# Node.net
KiCad netlist of a schematic drawn in EAGLE
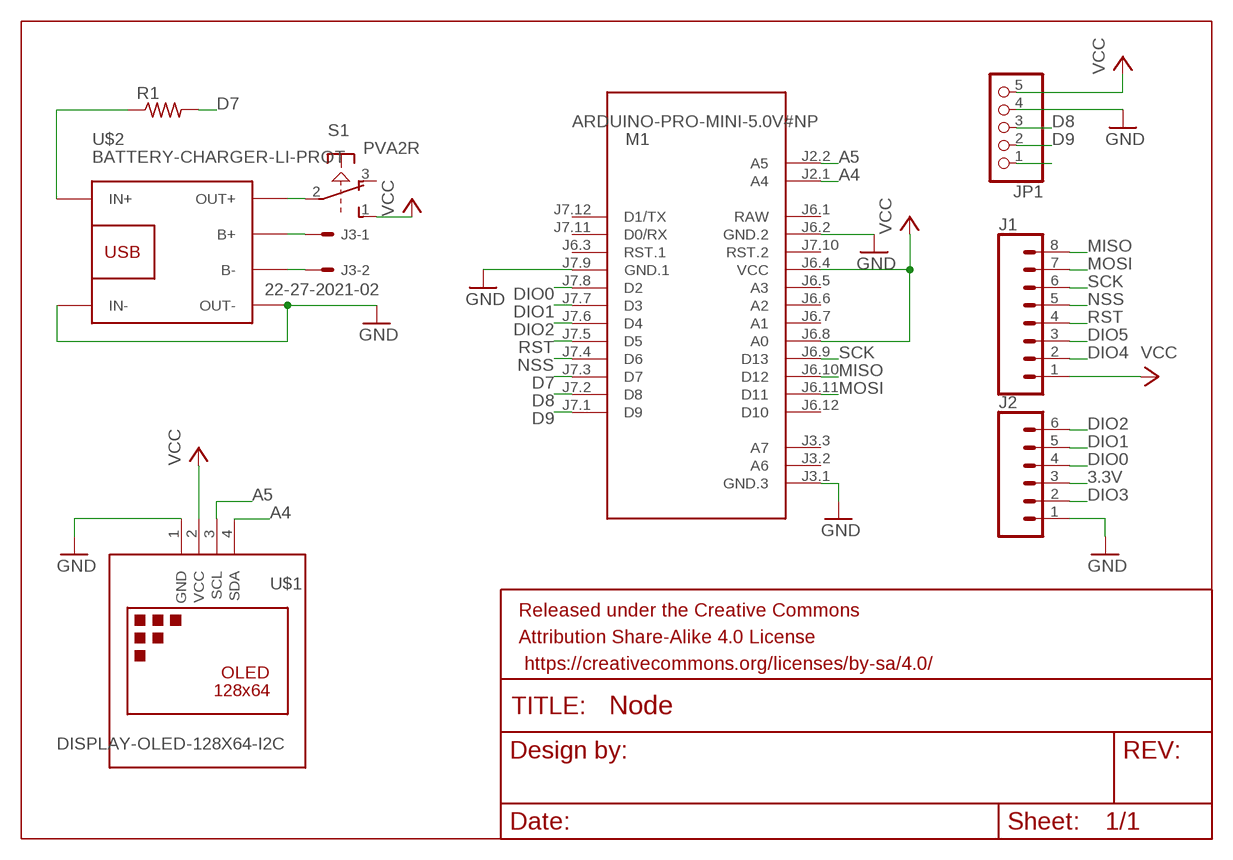
[diagram p0: schematic, sheet 1]

(export (version "E")
  (design (tool "Eeschema 10.0.6"))
  (components
    (comp (ref "FRAME1")
      (value "FRAME-LEDGER")
      (footprint "eagle-import:CREATIVE_COMMONS")
      (libsource (lib "eagle-import") (part "FRAME-LEDGER"))
    )
    (comp (ref "J1")
      (value "CONN_08\"")
      (footprint "eagle-import:1X08")
      (libsource (lib "eagle-import") (part "CONN_08{dblquote}"))
    )
    (comp (ref "J2")
      (value "CONN_06SILK_FEMALE_PTH")
      (footprint "eagle-import:1X06")
      (libsource (lib "eagle-import") (part "CONN_06SILK_FEMALE_PTH"))
    )
    (comp (ref "J3")
      (value "22-27-2021-02")
      (footprint "eagle-import:6410-02")
      (fields (field (name "MF") "MOLEX"))
      (libsource (lib "eagle-import") (part "22-?-0227-2021"))
    )
    (comp (ref "JP1")
      (value "PINHD-1X5/90")
      (footprint "eagle-import:1X05_90")
      (libsource (lib "eagle-import") (part "PINHD-1X5/90"))
    )
    (comp (ref "M1")
      (value "ARDUINO-PRO-MINI-5.0V#NP")
      (footprint "eagle-import:ARDUINO-PRO-MINI#NP")
      (libsource (lib "eagle-import") (part "ARDUINO-PRO-MINI-#NP5.0V"))
    )
    (comp (ref "R1")
      (value "R-US_R1206")
      (footprint "eagle-import:R1206")
      (libsource (lib "eagle-import") (part "R-US_R1206"))
    )
    (comp (ref "S1")
      (value "PVA2R")
      (footprint "eagle-import:PVA2R")
      (libsource (lib "eagle-import") (part "PVA2R"))
    )
    (comp (ref "U$1")
      (value "DISPLAY-OLED-128X64-I2C")
      (footprint "eagle-import:DISPLAY-OLED-128X64-I2C")
      (libsource (lib "eagle-import") (part "DISPLAY-OLED-128X64-I2C"))
    )
    (comp (ref "U$2")
      (value "BATTERY-CHARGER-LI-PROT")
      (footprint "eagle-import:BATTERY-CHARGER-LI-PROT")
      (libsource (lib "eagle-import") (part "BATTERY-CHARGER-LI-PROT"))
    )
  )
  (nets
    (net (code "1") (name "/3.3V") (class "Default")
      (node (ref "J2") (pin "3") (pinfunction "3_3") (pintype "passive"))
    )
    (net (code "2") (name "/A4") (class "Default")
      (node (ref "M1") (pin "J2.1") (pinfunction "A4_J2.1") (pintype "bidirectional"))
      (node (ref "U$1") (pin "4") (pinfunction "SDA_4") (pintype "bidirectional"))
    )
    (net (code "3") (name "/A5") (class "Default")
      (node (ref "M1") (pin "J2.2") (pinfunction "A5_J2.2") (pintype "bidirectional"))
      (node (ref "U$1") (pin "3") (pinfunction "SCL_3") (pintype "bidirectional"))
    )
    (net (code "4") (name "/D7") (class "Default")
      (node (ref "M1") (pin "J7.3") (pinfunction "D7_J7.3") (pintype "bidirectional"))
      (node (ref "R1") (pin "2") (pinfunction "2_2") (pintype "passive"))
    )
    (net (code "5") (name "/D8") (class "Default")
      (node (ref "JP1") (pin "3") (pinfunction "3_3") (pintype "passive"))
      (node (ref "M1") (pin "J7.2") (pinfunction "D8_J7.2") (pintype "bidirectional"))
    )
    (net (code "6") (name "/D9") (class "Default")
      (node (ref "JP1") (pin "2") (pinfunction "2_2") (pintype "passive"))
      (node (ref "M1") (pin "J7.1") (pinfunction "D9_J7.1") (pintype "bidirectional"))
    )
    (net (code "7") (name "/DIO0") (class "Default")
      (node (ref "J2") (pin "4") (pinfunction "4_4") (pintype "passive"))
      (node (ref "M1") (pin "J7.8") (pinfunction "D2_J7.8") (pintype "bidirectional"))
    )
    (net (code "8") (name "/DIO1") (class "Default")
      (node (ref "J2") (pin "5") (pinfunction "5_5") (pintype "passive"))
      (node (ref "M1") (pin "J7.7") (pinfunction "D3_J7.7") (pintype "bidirectional"))
    )
    (net (code "9") (name "/DIO2") (class "Default")
      (node (ref "J2") (pin "6") (pinfunction "6_6") (pintype "passive"))
      (node (ref "M1") (pin "J7.6") (pinfunction "D4_J7.6") (pintype "bidirectional"))
    )
    (net (code "10") (name "/DIO3") (class "Default")
      (node (ref "J2") (pin "2") (pinfunction "2_2") (pintype "passive"))
    )
    (net (code "11") (name "/DIO4") (class "Default")
      (node (ref "J1") (pin "2") (pinfunction "2_2") (pintype "passive"))
    )
    (net (code "12") (name "/DIO5") (class "Default")
      (node (ref "J1") (pin "3") (pinfunction "3_3") (pintype "passive"))
    )
    (net (code "13") (name "/MISO") (class "Default")
      (node (ref "J1") (pin "8") (pinfunction "8_8") (pintype "passive"))
      (node (ref "M1") (pin "J6.10") (pinfunction "D12_J6.10") (pintype "bidirectional"))
    )
    (net (code "14") (name "/MOSI") (class "Default")
      (node (ref "J1") (pin "7") (pinfunction "7_7") (pintype "passive"))
      (node (ref "M1") (pin "J6.11") (pinfunction "D11_J6.11") (pintype "bidirectional"))
    )
    (net (code "15") (name "/NSS") (class "Default")
      (node (ref "J1") (pin "5") (pinfunction "5_5") (pintype "passive"))
      (node (ref "M1") (pin "J7.4") (pinfunction "D6_J7.4") (pintype "bidirectional"))
    )
    (net (code "16") (name "/RAW") (class "Default")
      (node (ref "M1") (pin "J6.1") (pinfunction "RAW_J6.1") (pintype "power_in"))
    )
    (net (code "17") (name "/RST") (class "Default")
      (node (ref "J1") (pin "4") (pinfunction "4_4") (pintype "passive"))
      (node (ref "M1") (pin "J7.5") (pinfunction "D5_J7.5") (pintype "bidirectional"))
    )
    (net (code "18") (name "/SCK") (class "Default")
      (node (ref "J1") (pin "6") (pinfunction "6_6") (pintype "passive"))
      (node (ref "M1") (pin "J6.9") (pinfunction "D13_J6.9") (pintype "bidirectional"))
    )
    (net (code "19") (name "GND") (class "Default")
      (node (ref "J2") (pin "1") (pinfunction "1_1") (pintype "passive"))
      (node (ref "JP1") (pin "4") (pinfunction "4_4") (pintype "passive"))
      (node (ref "M1") (pin "J3.1") (pinfunction "GND.3_J3.1") (pintype "bidirectional"))
      (node (ref "M1") (pin "J6.2") (pinfunction "GND.2_J6.2") (pintype "power_in"))
      (node (ref "M1") (pin "J7.9") (pinfunction "GND.1_J7.9") (pintype "power_in"))
      (node (ref "U$1") (pin "1") (pinfunction "GND_1") (pintype "power_in"))
      (node (ref "U$2") (pin "IN-") (pinfunction "IN-_IN-") (pintype "bidirectional"))
      (node (ref "U$2") (pin "OUT-") (pinfunction "OUT-_OUT-") (pintype "bidirectional"))
    )
    (net (code "20") (name "Net-(J3A-S)") (class "Default")
      (node (ref "J3") (pin "1") (pinfunction "S_1") (pintype "passive"))
      (node (ref "U$2") (pin "B+") (pinfunction "B+_B+") (pintype "bidirectional"))
    )
    (net (code "21") (name "Net-(J3B-S)") (class "Default")
      (node (ref "J3") (pin "2") (pinfunction "S_2") (pintype "passive"))
      (node (ref "U$2") (pin "B-") (pinfunction "B-_B-") (pintype "bidirectional"))
    )
    (net (code "22") (name "Net-(R1-Pad1)") (class "Default")
      (node (ref "R1") (pin "1") (pinfunction "1_1") (pintype "passive"))
      (node (ref "U$2") (pin "IN+") (pinfunction "IN+_IN+") (pintype "bidirectional"))
    )
    (net (code "23") (name "Net-(S1A-P)") (class "Default")
      (node (ref "S1") (pin "2") (pinfunction "P_2") (pintype "passive"))
      (node (ref "U$2") (pin "OUT+") (pinfunction "OUT+_OUT+") (pintype "bidirectional"))
    )
    (net (code "24") (name "VCC") (class "Default")
      (node (ref "J1") (pin "1") (pinfunction "1_1") (pintype "passive"))
      (node (ref "JP1") (pin "5") (pinfunction "5_5") (pintype "passive"))
      (node (ref "M1") (pin "J6.4") (pinfunction "VCC_J6.4") (pintype "power_in"))
      (node (ref "M1") (pin "J6.8") (pinfunction "A0_J6.8") (pintype "bidirectional"))
      (node (ref "S1") (pin "1") (pinfunction "S_1") (pintype "passive"))
      (node (ref "U$1") (pin "2") (pinfunction "VCC_2") (pintype "power_in"))
    )
    (net (code "25") (name "unconnected-(JP1-Pad1)") (class "Default")
      (node (ref "JP1") (pin "1") (pinfunction "1_1") (pintype "passive"))
    )
    (net (code "26") (name "unconnected-(M1-A1-PadJ6.7)") (class "Default")
      (node (ref "M1") (pin "J6.7") (pinfunction "A1_J6.7") (pintype "bidirectional"))
    )
    (net (code "27") (name "unconnected-(M1-A2-PadJ6.6)") (class "Default")
      (node (ref "M1") (pin "J6.6") (pinfunction "A2_J6.6") (pintype "bidirectional"))
    )
    (net (code "28") (name "unconnected-(M1-A3-PadJ6.5)") (class "Default")
      (node (ref "M1") (pin "J6.5") (pinfunction "A3_J6.5") (pintype "bidirectional"))
    )
    (net (code "29") (name "unconnected-(M1-A6-PadJ3.2)") (class "Default")
      (node (ref "M1") (pin "J3.2") (pinfunction "A6_J3.2") (pintype "bidirectional"))
    )
    (net (code "30") (name "unconnected-(M1-A7-PadJ3.3)") (class "Default")
      (node (ref "M1") (pin "J3.3") (pinfunction "A7_J3.3") (pintype "bidirectional"))
    )
    (net (code "31") (name "unconnected-(M1-D0{slash}RX-PadJ7.11)") (class "Default")
      (node (ref "M1") (pin "J7.11") (pinfunction "D0/RX_J7.11") (pintype "bidirectional"))
    )
    (net (code "32") (name "unconnected-(M1-D1{slash}TX-PadJ7.12)") (class "Default")
      (node (ref "M1") (pin "J7.12") (pinfunction "D1/TX_J7.12") (pintype "bidirectional"))
    )
    (net (code "33") (name "unconnected-(M1-D10-PadJ6.12)") (class "Default")
      (node (ref "M1") (pin "J6.12") (pinfunction "D10_J6.12") (pintype "bidirectional"))
    )
    (net (code "34") (name "unconnected-(M1-RST.1-PadJ6.3)") (class "Default")
      (node (ref "M1") (pin "J6.3") (pinfunction "RST.1_J6.3") (pintype "bidirectional"))
    )
    (net (code "35") (name "unconnected-(M1-RST.2-PadJ7.10)") (class "Default")
      (node (ref "M1") (pin "J7.10") (pinfunction "RST.2_J7.10") (pintype "bidirectional"))
    )
    (net (code "36") (name "unconnected-(S1A-O-Pad3)") (class "Default")
      (node (ref "S1") (pin "3") (pinfunction "O_3") (pintype "passive"))
    )
  )
)
